# sensor_board_v0_54_trace.net
KiCad netlist of a schematic drawn in EAGLE
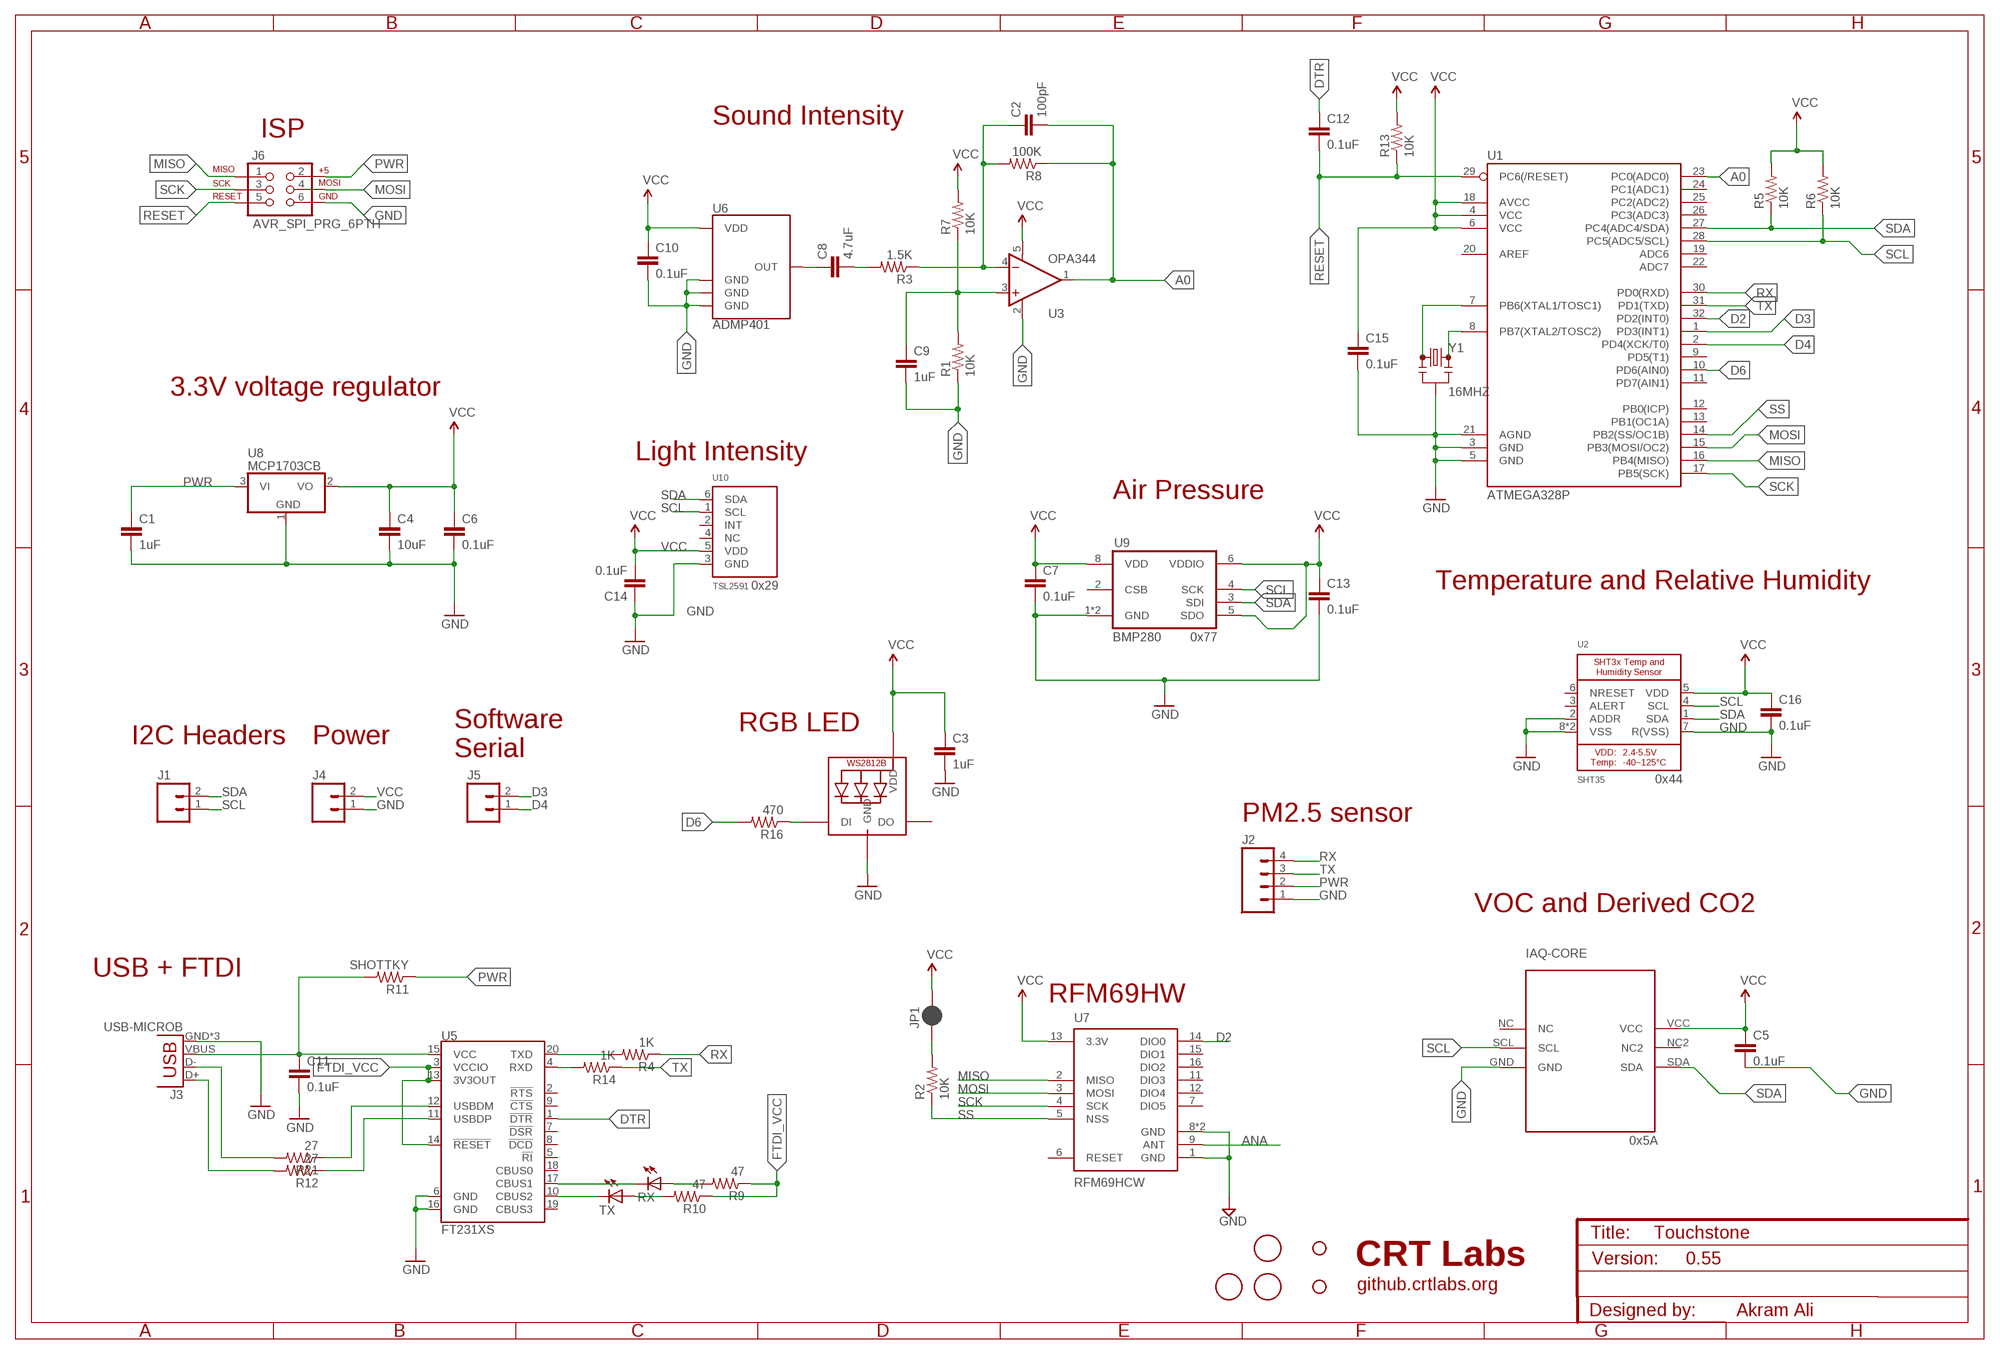
[diagram p0: schematic, sheet 1]

(export (version "E")
  (design (tool "Eeschema 10.0.6"))
  (components
    (comp (ref "C1")
      (value "1uF")
      (footprint "eagle-import:0805")
      (fields (field (name "MPN") "CC0805ZRY5V8BB105"))
      (libsource (lib "eagle-import") (part "CAP0805"))
    )
    (comp (ref "C2")
      (value "100pF")
      (footprint "eagle-import:0805")
      (fields (field (name "MPN") "CC0805JRNPOABN101"))
      (libsource (lib "eagle-import") (part "CAP0805"))
    )
    (comp (ref "C3")
      (value "1uF")
      (footprint "eagle-import:0805")
      (fields (field (name "MPN") "CC0805ZRY5V8BB105"))
      (libsource (lib "eagle-import") (part "CAP0805"))
    )
    (comp (ref "C4")
      (value "10uF")
      (footprint "eagle-import:0805")
      (fields (field (name "MPN") "CC0805KKX5R6BB106"))
      (libsource (lib "eagle-import") (part "CAP0805"))
    )
    (comp (ref "C5")
      (value "0.1uF")
      (footprint "eagle-import:0805")
      (fields (field (name "MPN") "CC0805KRX7R9BB104"))
      (libsource (lib "eagle-import") (part "SparkFun-Passives_CAP0805"))
    )
    (comp (ref "C6")
      (value "0.1uF")
      (footprint "eagle-import:0805")
      (fields (field (name "MPN") "CC0805KRX7R9BB104"))
      (libsource (lib "eagle-import") (part "CAP0805"))
    )
    (comp (ref "C7")
      (value "0.1uF")
      (footprint "eagle-import:0805")
      (fields (field (name "MPN") "CC0805KRX7R9BB104"))
      (libsource (lib "eagle-import") (part "SparkFun-Passives_CAP0805"))
    )
    (comp (ref "C8")
      (value "4.7uF")
      (footprint "eagle-import:0805")
      (fields (field (name "MPN") "CC0805KKX7R6BB475"))
      (libsource (lib "eagle-import") (part "CAP0805"))
    )
    (comp (ref "C9")
      (value "1uF")
      (footprint "eagle-import:0805")
      (fields (field (name "MPN") "CC0805ZRY5V8BB105"))
      (libsource (lib "eagle-import") (part "CAP0805"))
    )
    (comp (ref "C10")
      (value "0.1uF")
      (footprint "eagle-import:0805")
      (fields (field (name "MPN") "CC0805KRX7R9BB104"))
      (libsource (lib "eagle-import") (part "CAP0805"))
    )
    (comp (ref "C11")
      (value "0.1uF")
      (footprint "eagle-import:0805")
      (fields (field (name "MPN") "CC0805KRX7R9BB104"))
      (libsource (lib "eagle-import") (part "CAP0805"))
    )
    (comp (ref "C12")
      (value "0.1uF")
      (footprint "eagle-import:0805")
      (fields (field (name "MPN") "CC0805KRX7R9BB104"))
      (libsource (lib "eagle-import") (part "SparkFun-Passives_CAP0805"))
    )
    (comp (ref "C13")
      (value "0.1uF")
      (footprint "eagle-import:0805")
      (fields (field (name "MPN") "CC0805KRX7R9BB104"))
      (libsource (lib "eagle-import") (part "SparkFun-Passives_CAP0805"))
    )
    (comp (ref "C14")
      (value "0.1uF")
      (footprint "eagle-import:0805")
      (fields (field (name "MPN") "CC0805KRX7R9BB104"))
      (libsource (lib "eagle-import") (part "SparkFun-Passives_CAP0805"))
    )
    (comp (ref "C15")
      (value "0.1uF")
      (footprint "eagle-import:0805")
      (fields (field (name "MPN") "CC0805KRX7R9BB104"))
      (libsource (lib "eagle-import") (part "SparkFun-Passives_CAP0805"))
    )
    (comp (ref "C16")
      (value "0.1uF")
      (footprint "eagle-import:0805")
      (fields (field (name "MPN") "CC0805KRX7R9BB104"))
      (libsource (lib "eagle-import") (part "SparkFun-Passives_CAP0805"))
    )
    (comp (ref "H1")
      (value "STAND-OFF")
      (footprint "eagle-import:STAND-OFF")
      (libsource (lib "eagle-import") (part "STAND-OFF"))
    )
    (comp (ref "H2")
      (value "STAND-OFF")
      (footprint "eagle-import:STAND-OFF")
      (libsource (lib "eagle-import") (part "STAND-OFF"))
    )
    (comp (ref "IAQ-CORE")
      (value "IAQ-CORE")
      (footprint "eagle-import:IAQ-CORE")
      (fields (field (name "MPN") "IAQ-CORE C"))
      (libsource (lib "eagle-import") (part "IAQ-CORE"))
    )
    (comp (ref "J1")
      (value "M02PTH")
      (footprint "eagle-import:1X02")
      (libsource (lib "eagle-import") (part "M02PTH"))
    )
    (comp (ref "J2")
      (value "M04PTH")
      (footprint "eagle-import:1X04")
      (libsource (lib "eagle-import") (part "M04PTH"))
    )
    (comp (ref "J3")
      (value "USB-MICROB")
      (footprint "eagle-import:USB-MICROB")
      (fields (field (name "MPN") "47346-0001"))
      (libsource (lib "eagle-import") (part "USB-MICROB"))
    )
    (comp (ref "J4")
      (value "M02PTH")
      (footprint "eagle-import:1X02")
      (libsource (lib "eagle-import") (part "M02PTH"))
    )
    (comp (ref "J5")
      (value "M02PTH")
      (footprint "eagle-import:1X02")
      (libsource (lib "eagle-import") (part "M02PTH"))
    )
    (comp (ref "J6")
      (value "AVR_SPI_PRG_6PTH")
      (footprint "eagle-import:2X3")
      (libsource (lib "eagle-import") (part "AVR_SPI_PRG_6PTH"))
    )
    (comp (ref "JP1")
      (value "JUMPER-PAD-2-NC_BY_PASTEFULL-BOX-SILK")
      (footprint "eagle-import:PAD-JUMPER-2-NC_BY_PASTE_YES_SILK_FULL_BOX")
      (libsource (lib "eagle-import") (part "JUMPER-PAD-2-NC_BY_PASTEFULL-BOX-SILK"))
    )
    (comp (ref "LED1")
      (value "WS2812B3535")
      (footprint "eagle-import:LED3535")
      (fields (field (name "MPN") "SK6812 mini"))
      (libsource (lib "eagle-import") (part "WS2812B3535"))
    )
    (comp (ref "R1")
      (value "10K")
      (footprint "eagle-import:0805")
      (fields (field (name "MPN") "RC0805FR-0710KL"))
      (libsource (lib "eagle-import") (part "RESISTOR0805-RES"))
    )
    (comp (ref "R2")
      (value "10K")
      (footprint "eagle-import:0805")
      (fields (field (name "MPN") "RC0805FR-0710KL"))
      (libsource (lib "eagle-import") (part "RESISTOR0805-RES"))
    )
    (comp (ref "R3")
      (value "1.5K")
      (footprint "eagle-import:0805")
      (fields (field (name "MPN") "RC0805FR-071K5L "))
      (libsource (lib "eagle-import") (part "RESISTOR0805-RES"))
    )
    (comp (ref "R4")
      (value "1K")
      (footprint "eagle-import:0805")
      (fields (field (name "MPN") "RC0805FR-071KL"))
      (libsource (lib "eagle-import") (part "RESISTOR0805-RES"))
    )
    (comp (ref "R5")
      (value "10K")
      (footprint "eagle-import:0805")
      (fields (field (name "MPN") "RC0805FR-0710KL"))
      (libsource (lib "eagle-import") (part "SparkFun-Resistors_RESISTOR0805-RES"))
    )
    (comp (ref "R6")
      (value "10K")
      (footprint "eagle-import:0805")
      (fields (field (name "MPN") "RC0805FR-0710KL"))
      (libsource (lib "eagle-import") (part "SparkFun-Resistors_RESISTOR0805-RES"))
    )
    (comp (ref "R7")
      (value "10K")
      (footprint "eagle-import:0805")
      (fields (field (name "MPN") "RC0805FR-0710KL"))
      (libsource (lib "eagle-import") (part "RESISTOR0805-RES"))
    )
    (comp (ref "R8")
      (value "100K")
      (footprint "eagle-import:0805")
      (fields (field (name "MPN") "RC0805FR-07100KL "))
      (libsource (lib "eagle-import") (part "RESISTOR0805-RES"))
    )
    (comp (ref "R9")
      (value "47")
      (footprint "eagle-import:0805")
      (fields (field (name "MPN") "RC0805FR-0747RL "))
      (libsource (lib "eagle-import") (part "RESISTOR0805-RES"))
    )
    (comp (ref "R10")
      (value "47")
      (footprint "eagle-import:0805")
      (fields (field (name "MPN") "RC0805FR-0747RL "))
      (libsource (lib "eagle-import") (part "RESISTOR0805-RES"))
    )
    (comp (ref "R11")
      (value "SHOTTKY")
      (footprint "eagle-import:0805")
      (fields (field (name "MPN") "SD0805S040S0R5"))
      (libsource (lib "eagle-import") (part "RESISTOR0805-RES"))
    )
    (comp (ref "R12")
      (value "27")
      (footprint "eagle-import:0805")
      (fields (field (name "MPN") "RC0805FR-0727RL "))
      (libsource (lib "eagle-import") (part "RESISTOR0805-RES"))
    )
    (comp (ref "R13")
      (value "10K")
      (footprint "eagle-import:0805")
      (fields (field (name "MPN") "RC0805FR-0710KL"))
      (libsource (lib "eagle-import") (part "RESISTOR0805-RES"))
    )
    (comp (ref "R14")
      (value "1K")
      (footprint "eagle-import:0805")
      (fields (field (name "MPN") "RC0805FR-071KL"))
      (libsource (lib "eagle-import") (part "RESISTOR0805-RES"))
    )
    (comp (ref "R16")
      (value "470")
      (footprint "eagle-import:R0603")
      (fields (field (name "MPN") "RC0805FR-07470RL "))
      (libsource (lib "eagle-import") (part "R-US_R0603"))
    )
    (comp (ref "R21")
      (value "27")
      (footprint "eagle-import:0805")
      (fields (field (name "MPN") "RC0805FR-0727RL "))
      (libsource (lib "eagle-import") (part "RESISTOR0805-RES"))
    )
    (comp (ref "RX")
      (value "LEDCHIPLED_0805")
      (footprint "eagle-import:CHIPLED_0805")
      (fields (field (name "MPN") "LG R971-KN-1"))
      (libsource (lib "eagle-import") (part "LEDCHIPLED_0805"))
    )
    (comp (ref "TX")
      (value "LEDCHIPLED_0805")
      (footprint "eagle-import:CHIPLED_0805")
      (fields (field (name "MPN") "LG R971-KN-1"))
      (libsource (lib "eagle-import") (part "LEDCHIPLED_0805"))
    )
    (comp (ref "U$1")
      (value "FIDUCIAL")
      (footprint "eagle-import:FIDUCIAL_1MM")
      (libsource (lib "eagle-import") (part "FIDUCIAL"))
    )
    (comp (ref "U$2")
      (value "FIDUCIAL")
      (footprint "eagle-import:FIDUCIAL_1MM")
      (libsource (lib "eagle-import") (part "FIDUCIAL"))
    )
    (comp (ref "U$3")
      (value "FIDUCIAL")
      (footprint "eagle-import:FIDUCIAL_1MM")
      (libsource (lib "eagle-import") (part "FIDUCIAL"))
    )
    (comp (ref "U1")
      (value "ATMEGA328P")
      (footprint "eagle-import:TQFP32-08")
      (fields (field (name "MPN") "ATMEGA328PB-AU"))
      (libsource (lib "eagle-import") (part "ATMEGA328P_TQFP"))
    )
    (comp (ref "U2")
      (value "SHT35")
      (footprint "eagle-import:SHT3X")
      (fields (field (name "MPN") "SHT35-DIS-B"))
      (libsource (lib "eagle-import") (part "SHT3X"))
    )
    (comp (ref "U3")
      (value "OPA344")
      (footprint "eagle-import:SOT23-5")
      (fields (field (name "MPN") "OPA344NA/3K"))
      (libsource (lib "eagle-import") (part "OPA344"))
    )
    (comp (ref "U5")
      (value "FT231XS")
      (footprint "eagle-import:SSOP20_L")
      (fields (field (name "MPN") "FT231XQ-R"))
      (libsource (lib "eagle-import") (part "FT231XS"))
    )
    (comp (ref "U6")
      (value "ADMP401")
      (footprint "eagle-import:ADMP401")
      (fields (field (name "MPN") "INMP401ACEZ-R7"))
      (libsource (lib "eagle-import") (part "ADMP401"))
    )
    (comp (ref "U7")
      (value "RFM69HCW")
      (footprint "eagle-import:RFM69HCW-XXXS2")
      (fields (field (name "MPN") "RFM69HW"))
      (libsource (lib "eagle-import") (part "RFM69HCW"))
    )
    (comp (ref "U8")
      (value "MCP1703CB")
      (footprint "eagle-import:SOT23")
      (fields (field (name "MPN") "MCP1703T-2502E/CB"))
      (libsource (lib "eagle-import") (part "MCP1703CB"))
    )
    (comp (ref "U9")
      (value "BMP280")
      (footprint "eagle-import:BMP280")
      (libsource (lib "eagle-import") (part "BMP280"))
    )
    (comp (ref "U10")
      (value "TSL2591")
      (footprint "eagle-import:DFN6_TAOS")
      (fields (field (name "MPN") "TSL25911FN "))
      (libsource (lib "eagle-import") (part "LIGHT_TSL2591"))
    )
    (comp (ref "Y1")
      (value "16MHZ")
      (footprint "eagle-import:RESONATOR-SMD")
      (fields (field (name "MPN") "CSTCE16M0V53-R0"))
      (libsource (lib "eagle-import") (part "RESONATOR16MHZ"))
    )
  )
  (nets
    (net (code "1") (name "/ANA") (class "Default")
      (node (ref "U7") (pin "9") (pinfunction "ANT_9") (pintype "passive"))
    )
    (net (code "2") (name "A0") (class "Default")
      (node (ref "C2") (pin "2") (pinfunction "2_2") (pintype "passive"))
      (node (ref "R8") (pin "1") (pinfunction "1_1") (pintype "passive"))
      (node (ref "U1") (pin "23") (pinfunction "PC0(ADC0)_23") (pintype "bidirectional"))
      (node (ref "U3") (pin "1") (pinfunction "OUT_1") (pintype "output"))
    )
    (net (code "3") (name "D2") (class "Default")
      (node (ref "U1") (pin "32") (pinfunction "PD2(INT0)_32") (pintype "bidirectional"))
      (node (ref "U7") (pin "14") (pinfunction "DIO0_14") (pintype "bidirectional"))
    )
    (net (code "4") (name "D3") (class "Default")
      (node (ref "J5") (pin "2") (pinfunction "2_2") (pintype "passive"))
      (node (ref "U1") (pin "1") (pinfunction "PD3(INT1)_1") (pintype "bidirectional"))
    )
    (net (code "5") (name "D4") (class "Default")
      (node (ref "J5") (pin "1") (pinfunction "1_1") (pintype "passive"))
      (node (ref "U1") (pin "2") (pinfunction "PD4(XCK/T0)_2") (pintype "bidirectional"))
    )
    (net (code "6") (name "D6") (class "Default")
      (node (ref "R16") (pin "2") (pinfunction "2_2") (pintype "passive"))
      (node (ref "U1") (pin "10") (pinfunction "PD6(AIN0)_10") (pintype "bidirectional"))
    )
    (net (code "7") (name "DTR") (class "Default")
      (node (ref "C12") (pin "1") (pinfunction "1_1") (pintype "passive"))
      (node (ref "U5") (pin "1") (pinfunction "~{DTR}_1") (pintype "bidirectional"))
    )
    (net (code "8") (name "FTDI_VCC") (class "Default")
      (node (ref "R10") (pin "1") (pinfunction "1_1") (pintype "passive"))
      (node (ref "R9") (pin "1") (pinfunction "1_1") (pintype "passive"))
      (node (ref "U5") (pin "13") (pinfunction "3V3OUT_13") (pintype "bidirectional"))
      (node (ref "U5") (pin "14") (pinfunction "~{RESET}_14") (pintype "bidirectional"))
      (node (ref "U5") (pin "3") (pinfunction "VCCIO_3") (pintype "bidirectional"))
    )
    (net (code "9") (name "GND") (class "Default")
      (node (ref "C1") (pin "2") (pinfunction "2_2") (pintype "passive"))
      (node (ref "C10") (pin "2") (pinfunction "2_2") (pintype "passive"))
      (node (ref "C11") (pin "2") (pinfunction "2_2") (pintype "passive"))
      (node (ref "C13") (pin "2") (pinfunction "2_2") (pintype "passive"))
      (node (ref "C14") (pin "1") (pinfunction "1_1") (pintype "passive"))
      (node (ref "C15") (pin "2") (pinfunction "2_2") (pintype "passive"))
      (node (ref "C16") (pin "2") (pinfunction "2_2") (pintype "passive"))
      (node (ref "C3") (pin "2") (pinfunction "2_2") (pintype "passive"))
      (node (ref "C4") (pin "2") (pinfunction "2_2") (pintype "passive"))
      (node (ref "C5") (pin "2") (pinfunction "2_2") (pintype "passive"))
      (node (ref "C6") (pin "2") (pinfunction "2_2") (pintype "passive"))
      (node (ref "C7") (pin "2") (pinfunction "2_2") (pintype "passive"))
      (node (ref "C9") (pin "2") (pinfunction "2_2") (pintype "passive"))
      (node (ref "IAQ-CORE") (pin "GND") (pinfunction "GND_GND") (pintype "bidirectional"))
      (node (ref "J2") (pin "1") (pinfunction "1_1") (pintype "passive"))
      (node (ref "J3") (pin "GND") (pinfunction "GND_GND") (pintype "bidirectional"))
      (node (ref "J3") (pin "MT1") (pinfunction "GND_MT1") (pintype "bidirectional"))
      (node (ref "J3") (pin "MT2") (pinfunction "GND_MT2") (pintype "bidirectional"))
      (node (ref "J4") (pin "1") (pinfunction "1_1") (pintype "passive"))
      (node (ref "J6") (pin "6") (pinfunction "6_6") (pintype "passive"))
      (node (ref "LED1") (pin "4") (pinfunction "GND_4") (pintype "power_in"))
      (node (ref "R1") (pin "1") (pinfunction "1_1") (pintype "passive"))
      (node (ref "U1") (pin "21") (pinfunction "AGND_21") (pintype "bidirectional"))
      (node (ref "U1") (pin "3") (pinfunction "GND_3") (pintype "bidirectional"))
      (node (ref "U1") (pin "5") (pinfunction "GND_5") (pintype "bidirectional"))
      (node (ref "U10") (pin "3") (pinfunction "GND_3") (pintype "power_in"))
      (node (ref "U2") (pin "2") (pinfunction "ADDR_2") (pintype "bidirectional"))
      (node (ref "U2") (pin "7") (pinfunction "R(VSS)_7") (pintype "bidirectional"))
      (node (ref "U2") (pin "8") (pinfunction "VSS_8") (pintype "power_in"))
      (node (ref "U2") (pin "THERMAL") (pinfunction "VSS_THERMAL") (pintype "power_in"))
      (node (ref "U3") (pin "2") (pinfunction "V-_2") (pintype "power_in"))
      (node (ref "U5") (pin "16") (pinfunction "GND_16") (pintype "bidirectional"))
      (node (ref "U5") (pin "6") (pinfunction "GND_6") (pintype "bidirectional"))
      (node (ref "U6") (pin "2") (pinfunction "GND_2") (pintype "bidirectional"))
      (node (ref "U6") (pin "4") (pinfunction "GND_4") (pintype "bidirectional"))
      (node (ref "U6") (pin "6") (pinfunction "GND_6") (pintype "bidirectional"))
      (node (ref "U7") (pin "1") (pinfunction "GND_1") (pintype "power_in"))
      (node (ref "U7") (pin "10") (pinfunction "GND_10") (pintype "power_in"))
      (node (ref "U7") (pin "8") (pinfunction "GND_8") (pintype "power_in"))
      (node (ref "U8") (pin "1") (pinfunction "GND_1") (pintype "passive"))
      (node (ref "U9") (pin "1") (pinfunction "GND_1") (pintype "power_in"))
      (node (ref "U9") (pin "7") (pinfunction "GND_7") (pintype "power_in"))
      (node (ref "Y1") (pin "2") (pinfunction "2_2") (pintype "passive"))
    )
    (net (code "10") (name "MISO") (class "Default")
      (node (ref "J6") (pin "1") (pinfunction "1_1") (pintype "passive"))
      (node (ref "U1") (pin "16") (pinfunction "PB4(MISO)_16") (pintype "bidirectional"))
      (node (ref "U7") (pin "2") (pinfunction "MISO_2") (pintype "bidirectional"))
    )
    (net (code "11") (name "MOSI") (class "Default")
      (node (ref "J6") (pin "4") (pinfunction "4_4") (pintype "passive"))
      (node (ref "U1") (pin "15") (pinfunction "PB3(MOSI/OC2)_15") (pintype "bidirectional"))
      (node (ref "U7") (pin "3") (pinfunction "MOSI_3") (pintype "input"))
    )
    (net (code "12") (name "Net-(C8-Pad2)") (class "Default")
      (node (ref "C8") (pin "2") (pinfunction "2_2") (pintype "passive"))
      (node (ref "R3") (pin "2") (pinfunction "2_2") (pintype "passive"))
    )
    (net (code "13") (name "Net-(J3-PadD+)") (class "Default")
      (node (ref "J3") (pin "D+") (pinfunction "D+_D+") (pintype "bidirectional"))
      (node (ref "R12") (pin "2") (pinfunction "2_2") (pintype "passive"))
    )
    (net (code "14") (name "Net-(J3-PadD-)") (class "Default")
      (node (ref "J3") (pin "D-") (pinfunction "D-_D-") (pintype "bidirectional"))
      (node (ref "R21") (pin "2") (pinfunction "2_2") (pintype "passive"))
    )
    (net (code "15") (name "Net-(JP1-Pad1)") (class "Default")
      (node (ref "JP1") (pin "1") (pinfunction "1_1") (pintype "passive"))
      (node (ref "R2") (pin "2") (pinfunction "2_2") (pintype "passive"))
    )
    (net (code "16") (name "Net-(LED1-DI)") (class "Default")
      (node (ref "LED1") (pin "1") (pinfunction "DI_1") (pintype "input"))
      (node (ref "R16") (pin "1") (pinfunction "1_1") (pintype "passive"))
    )
    (net (code "17") (name "Net-(R9-Pad2)") (class "Default")
      (node (ref "R9") (pin "2") (pinfunction "2_2") (pintype "passive"))
      (node (ref "RX") (pin "A") (pinfunction "A_A") (pintype "passive"))
    )
    (net (code "18") (name "Net-(R10-Pad2)") (class "Default")
      (node (ref "R10") (pin "2") (pinfunction "2_2") (pintype "passive"))
      (node (ref "TX") (pin "A") (pinfunction "A_A") (pintype "passive"))
    )
    (net (code "19") (name "Net-(U1-PB6(XTAL1{slash}TOSC1))") (class "Default")
      (node (ref "U1") (pin "7") (pinfunction "PB6(XTAL1/TOSC1)_7") (pintype "bidirectional"))
      (node (ref "Y1") (pin "1") (pinfunction "1_1") (pintype "passive"))
    )
    (net (code "20") (name "Net-(U1-PB7(XTAL2{slash}TOSC2))") (class "Default")
      (node (ref "U1") (pin "8") (pinfunction "PB7(XTAL2/TOSC2)_8") (pintype "bidirectional"))
      (node (ref "Y1") (pin "3") (pinfunction "3_3") (pintype "passive"))
    )
    (net (code "21") (name "Net-(U3-+IN)") (class "Default")
      (node (ref "C9") (pin "1") (pinfunction "1_1") (pintype "passive"))
      (node (ref "R1") (pin "2") (pinfunction "2_2") (pintype "passive"))
      (node (ref "R7") (pin "1") (pinfunction "1_1") (pintype "passive"))
      (node (ref "U3") (pin "3") (pinfunction "+IN_3") (pintype "input"))
    )
    (net (code "22") (name "Net-(U3--IN)") (class "Default")
      (node (ref "C2") (pin "1") (pinfunction "1_1") (pintype "passive"))
      (node (ref "R3") (pin "1") (pinfunction "1_1") (pintype "passive"))
      (node (ref "R8") (pin "2") (pinfunction "2_2") (pintype "passive"))
      (node (ref "U3") (pin "4") (pinfunction "-IN_4") (pintype "input"))
    )
    (net (code "23") (name "Net-(U5-CBUS1)") (class "Default")
      (node (ref "RX") (pin "C") (pinfunction "C_C") (pintype "passive"))
      (node (ref "U5") (pin "17") (pinfunction "CBUS1_17") (pintype "bidirectional"))
    )
    (net (code "24") (name "Net-(U5-CBUS2)") (class "Default")
      (node (ref "TX") (pin "C") (pinfunction "C_C") (pintype "passive"))
      (node (ref "U5") (pin "10") (pinfunction "CBUS2_10") (pintype "bidirectional"))
    )
    (net (code "25") (name "Net-(U5-RXD)") (class "Default")
      (node (ref "R14") (pin "2") (pinfunction "2_2") (pintype "passive"))
      (node (ref "U5") (pin "4") (pinfunction "RXD_4") (pintype "bidirectional"))
    )
    (net (code "26") (name "Net-(U5-TXD)") (class "Default")
      (node (ref "R4") (pin "2") (pinfunction "2_2") (pintype "passive"))
      (node (ref "U5") (pin "20") (pinfunction "TXD_20") (pintype "bidirectional"))
    )
    (net (code "27") (name "Net-(U5-USBDM)") (class "Default")
      (node (ref "R21") (pin "1") (pinfunction "1_1") (pintype "passive"))
      (node (ref "U5") (pin "12") (pinfunction "USBDM_12") (pintype "bidirectional"))
    )
    (net (code "28") (name "Net-(U5-USBDP)") (class "Default")
      (node (ref "R12") (pin "1") (pinfunction "1_1") (pintype "passive"))
      (node (ref "U5") (pin "11") (pinfunction "USBDP_11") (pintype "bidirectional"))
    )
    (net (code "29") (name "Net-(U5-VCC)") (class "Default")
      (node (ref "C11") (pin "1") (pinfunction "1_1") (pintype "passive"))
      (node (ref "J3") (pin "VBUS") (pinfunction "VBUS_VBUS") (pintype "bidirectional"))
      (node (ref "R11") (pin "2") (pinfunction "2_2") (pintype "passive"))
      (node (ref "U5") (pin "15") (pinfunction "VCC_15") (pintype "bidirectional"))
    )
    (net (code "30") (name "Net-(U6-OUT)") (class "Default")
      (node (ref "C8") (pin "1") (pinfunction "1_1") (pintype "passive"))
      (node (ref "U6") (pin "1") (pinfunction "OUT_1") (pintype "bidirectional"))
    )
    (net (code "31") (name "PWR") (class "Default")
      (node (ref "C1") (pin "1") (pinfunction "1_1") (pintype "passive"))
      (node (ref "J2") (pin "2") (pinfunction "2_2") (pintype "passive"))
      (node (ref "J6") (pin "2") (pinfunction "2_2") (pintype "passive"))
      (node (ref "R11") (pin "1") (pinfunction "1_1") (pintype "passive"))
      (node (ref "U8") (pin "3") (pinfunction "VI_3") (pintype "input"))
    )
    (net (code "32") (name "RESET") (class "Default")
      (node (ref "C12") (pin "2") (pinfunction "2_2") (pintype "passive"))
      (node (ref "J6") (pin "5") (pinfunction "5_5") (pintype "passive"))
      (node (ref "R13") (pin "1") (pinfunction "1_1") (pintype "passive"))
      (node (ref "U1") (pin "29") (pinfunction "PC6(/RESET)_29") (pintype "bidirectional"))
    )
    (net (code "33") (name "RX") (class "Default")
      (node (ref "J2") (pin "4") (pinfunction "4_4") (pintype "passive"))
      (node (ref "R4") (pin "1") (pinfunction "1_1") (pintype "passive"))
      (node (ref "U1") (pin "30") (pinfunction "PD0(RXD)_30") (pintype "bidirectional"))
    )
    (net (code "34") (name "SCK") (class "Default")
      (node (ref "J6") (pin "3") (pinfunction "3_3") (pintype "passive"))
      (node (ref "U1") (pin "17") (pinfunction "PB5(SCK)_17") (pintype "bidirectional"))
      (node (ref "U7") (pin "4") (pinfunction "SCK_4") (pintype "input"))
    )
    (net (code "35") (name "SCL") (class "Default")
      (node (ref "IAQ-CORE") (pin "SCL") (pinfunction "SCL_SCL") (pintype "bidirectional"))
      (node (ref "J1") (pin "1") (pinfunction "1_1") (pintype "passive"))
      (node (ref "R6") (pin "1") (pinfunction "1_1") (pintype "passive"))
      (node (ref "U1") (pin "28") (pinfunction "PC5(ADC5/SCL)_28") (pintype "bidirectional"))
      (node (ref "U10") (pin "1") (pinfunction "SCL_1") (pintype "bidirectional"))
      (node (ref "U2") (pin "4") (pinfunction "SCL_4") (pintype "bidirectional"))
      (node (ref "U9") (pin "4") (pinfunction "SCK_4") (pintype "bidirectional"))
    )
    (net (code "36") (name "SDA") (class "Default")
      (node (ref "IAQ-CORE") (pin "SDA") (pinfunction "SDA_SDA") (pintype "bidirectional"))
      (node (ref "J1") (pin "2") (pinfunction "2_2") (pintype "passive"))
      (node (ref "R5") (pin "1") (pinfunction "1_1") (pintype "passive"))
      (node (ref "U1") (pin "27") (pinfunction "PC4(ADC4/SDA)_27") (pintype "bidirectional"))
      (node (ref "U10") (pin "6") (pinfunction "SDA_6") (pintype "bidirectional"))
      (node (ref "U2") (pin "1") (pinfunction "SDA_1") (pintype "bidirectional"))
      (node (ref "U9") (pin "3") (pinfunction "SDI_3") (pintype "bidirectional"))
    )
    (net (code "37") (name "SS") (class "Default")
      (node (ref "R2") (pin "1") (pinfunction "1_1") (pintype "passive"))
      (node (ref "U1") (pin "14") (pinfunction "PB2(SS/OC1B)_14") (pintype "bidirectional"))
      (node (ref "U7") (pin "5") (pinfunction "NSS_5") (pintype "input"))
    )
    (net (code "38") (name "TX") (class "Default")
      (node (ref "J2") (pin "3") (pinfunction "3_3") (pintype "passive"))
      (node (ref "R14") (pin "1") (pinfunction "1_1") (pintype "passive"))
      (node (ref "U1") (pin "31") (pinfunction "PD1(TXD)_31") (pintype "bidirectional"))
    )
    (net (code "39") (name "VCC") (class "Default")
      (node (ref "C10") (pin "1") (pinfunction "1_1") (pintype "passive"))
      (node (ref "C13") (pin "1") (pinfunction "1_1") (pintype "passive"))
      (node (ref "C14") (pin "2") (pinfunction "2_2") (pintype "passive"))
      (node (ref "C15") (pin "1") (pinfunction "1_1") (pintype "passive"))
      (node (ref "C16") (pin "1") (pinfunction "1_1") (pintype "passive"))
      (node (ref "C3") (pin "1") (pinfunction "1_1") (pintype "passive"))
      (node (ref "C4") (pin "1") (pinfunction "1_1") (pintype "passive"))
      (node (ref "C5") (pin "1") (pinfunction "1_1") (pintype "passive"))
      (node (ref "C6") (pin "1") (pinfunction "1_1") (pintype "passive"))
      (node (ref "C7") (pin "1") (pinfunction "1_1") (pintype "passive"))
      (node (ref "IAQ-CORE") (pin "VCC") (pinfunction "VCC_VCC") (pintype "bidirectional"))
      (node (ref "J4") (pin "2") (pinfunction "2_2") (pintype "passive"))
      (node (ref "JP1") (pin "2") (pinfunction "2_2") (pintype "passive"))
      (node (ref "LED1") (pin "2") (pinfunction "VDD_2") (pintype "power_in"))
      (node (ref "R13") (pin "2") (pinfunction "2_2") (pintype "passive"))
      (node (ref "R5") (pin "2") (pinfunction "2_2") (pintype "passive"))
      (node (ref "R6") (pin "2") (pinfunction "2_2") (pintype "passive"))
      (node (ref "R7") (pin "2") (pinfunction "2_2") (pintype "passive"))
      (node (ref "U1") (pin "18") (pinfunction "AVCC_18") (pintype "bidirectional"))
      (node (ref "U1") (pin "4") (pinfunction "VCC_4") (pintype "bidirectional"))
      (node (ref "U1") (pin "6") (pinfunction "VCC_6") (pintype "bidirectional"))
      (node (ref "U10") (pin "5") (pinfunction "VDD_5") (pintype "power_in"))
      (node (ref "U2") (pin "5") (pinfunction "VDD_5") (pintype "power_in"))
      (node (ref "U3") (pin "5") (pinfunction "V+_5") (pintype "power_in"))
      (node (ref "U6") (pin "5") (pinfunction "VDD_5") (pintype "bidirectional"))
      (node (ref "U7") (pin "13") (pinfunction "3.3V_13") (pintype "power_in"))
      (node (ref "U8") (pin "2") (pinfunction "VO_2") (pintype "passive"))
      (node (ref "U9") (pin "5") (pinfunction "SDO_5") (pintype "input"))
      (node (ref "U9") (pin "6") (pinfunction "VDDIO_6") (pintype "power_in"))
      (node (ref "U9") (pin "8") (pinfunction "VDD_8") (pintype "power_in"))
    )
    (net (code "40") (name "unconnected-(IAQ-CORE-PadNC)") (class "Default")
      (node (ref "IAQ-CORE") (pin "NC") (pinfunction "NC_NC") (pintype "bidirectional"))
    )
    (net (code "41") (name "unconnected-(IAQ-CORE-PadNC2)") (class "Default")
      (node (ref "IAQ-CORE") (pin "NC2") (pinfunction "NC2_NC2") (pintype "bidirectional"))
    )
    (net (code "42") (name "unconnected-(LED1-DO-Pad3)") (class "Default")
      (node (ref "LED1") (pin "3") (pinfunction "DO_3") (pintype "output"))
    )
    (net (code "43") (name "unconnected-(U1-ADC6-Pad19)") (class "Default")
      (node (ref "U1") (pin "19") (pinfunction "ADC6_19") (pintype "bidirectional"))
    )
    (net (code "44") (name "unconnected-(U1-ADC7-Pad22)") (class "Default")
      (node (ref "U1") (pin "22") (pinfunction "ADC7_22") (pintype "bidirectional"))
    )
    (net (code "45") (name "unconnected-(U1-AREF-Pad20)") (class "Default")
      (node (ref "U1") (pin "20") (pinfunction "AREF_20") (pintype "bidirectional"))
    )
    (net (code "46") (name "unconnected-(U1-PB0(ICP)-Pad12)") (class "Default")
      (node (ref "U1") (pin "12") (pinfunction "PB0(ICP)_12") (pintype "bidirectional"))
    )
    (net (code "47") (name "unconnected-(U1-PB1(OC1A)-Pad13)") (class "Default")
      (node (ref "U1") (pin "13") (pinfunction "PB1(OC1A)_13") (pintype "bidirectional"))
    )
    (net (code "48") (name "unconnected-(U1-PC1(ADC1)-Pad24)") (class "Default")
      (node (ref "U1") (pin "24") (pinfunction "PC1(ADC1)_24") (pintype "bidirectional"))
    )
    (net (code "49") (name "unconnected-(U1-PC2(ADC2)-Pad25)") (class "Default")
      (node (ref "U1") (pin "25") (pinfunction "PC2(ADC2)_25") (pintype "bidirectional"))
    )
    (net (code "50") (name "unconnected-(U1-PC3(ADC3)-Pad26)") (class "Default")
      (node (ref "U1") (pin "26") (pinfunction "PC3(ADC3)_26") (pintype "bidirectional"))
    )
    (net (code "51") (name "unconnected-(U1-PD5(T1)-Pad9)") (class "Default")
      (node (ref "U1") (pin "9") (pinfunction "PD5(T1)_9") (pintype "bidirectional"))
    )
    (net (code "52") (name "unconnected-(U1-PD7(AIN1)-Pad11)") (class "Default")
      (node (ref "U1") (pin "11") (pinfunction "PD7(AIN1)_11") (pintype "bidirectional"))
    )
    (net (code "53") (name "unconnected-(U2-ALERT-Pad3)") (class "Default")
      (node (ref "U2") (pin "3") (pinfunction "ALERT_3") (pintype "bidirectional"))
    )
    (net (code "54") (name "unconnected-(U2-NRESET-Pad6)") (class "Default")
      (node (ref "U2") (pin "6") (pinfunction "NRESET_6") (pintype "bidirectional"))
    )
    (net (code "55") (name "unconnected-(U5-CBUS0-Pad18)") (class "Default")
      (node (ref "U5") (pin "18") (pinfunction "CBUS0_18") (pintype "bidirectional"))
    )
    (net (code "56") (name "unconnected-(U5-CBUS3-Pad19)") (class "Default")
      (node (ref "U5") (pin "19") (pinfunction "CBUS3_19") (pintype "bidirectional"))
    )
    (net (code "57") (name "unconnected-(U5-~{CTS}-Pad9)") (class "Default")
      (node (ref "U5") (pin "9") (pinfunction "~{CTS}_9") (pintype "bidirectional"))
    )
    (net (code "58") (name "unconnected-(U5-~{DCD}-Pad8)") (class "Default")
      (node (ref "U5") (pin "8") (pinfunction "~{DCD}_8") (pintype "bidirectional"))
    )
    (net (code "59") (name "unconnected-(U5-~{DSR}-Pad7)") (class "Default")
      (node (ref "U5") (pin "7") (pinfunction "~{DSR}_7") (pintype "bidirectional"))
    )
    (net (code "60") (name "unconnected-(U5-~{RI}-Pad5)") (class "Default")
      (node (ref "U5") (pin "5") (pinfunction "~{RI}_5") (pintype "bidirectional"))
    )
    (net (code "61") (name "unconnected-(U5-~{RTS}-Pad2)") (class "Default")
      (node (ref "U5") (pin "2") (pinfunction "~{RTS}_2") (pintype "bidirectional"))
    )
    (net (code "62") (name "unconnected-(U7-DIO1-Pad15)") (class "Default")
      (node (ref "U7") (pin "15") (pinfunction "DIO1_15") (pintype "bidirectional"))
    )
    (net (code "63") (name "unconnected-(U7-DIO2-Pad16)") (class "Default")
      (node (ref "U7") (pin "16") (pinfunction "DIO2_16") (pintype "bidirectional"))
    )
    (net (code "64") (name "unconnected-(U7-DIO3-Pad11)") (class "Default")
      (node (ref "U7") (pin "11") (pinfunction "DIO3_11") (pintype "bidirectional"))
    )
    (net (code "65") (name "unconnected-(U7-DIO4-Pad12)") (class "Default")
      (node (ref "U7") (pin "12") (pinfunction "DIO4_12") (pintype "bidirectional"))
    )
    (net (code "66") (name "unconnected-(U7-DIO5-Pad7)") (class "Default")
      (node (ref "U7") (pin "7") (pinfunction "DIO5_7") (pintype "bidirectional"))
    )
    (net (code "67") (name "unconnected-(U7-RESET-Pad6)") (class "Default")
      (node (ref "U7") (pin "6") (pinfunction "RESET_6") (pintype "input"))
    )
    (net (code "68") (name "unconnected-(U9-CSB-Pad2)") (class "Default")
      (node (ref "U9") (pin "2") (pinfunction "CSB_2") (pintype "input"))
    )
    (net (code "69") (name "unconnected-(U10-INT-Pad2)") (class "Default")
      (node (ref "U10") (pin "2") (pinfunction "INT_2") (pintype "output"))
    )
    (net (code "70") (name "unconnected-(U10-NC-Pad4)") (class "Default")
      (node (ref "U10") (pin "4") (pinfunction "NC_4") (pintype "no_connect"))
    )
  )
)
